# SL_LCD_SW_LED_2E.net
KiCad netlist of a schematic drawn in Altium Designer
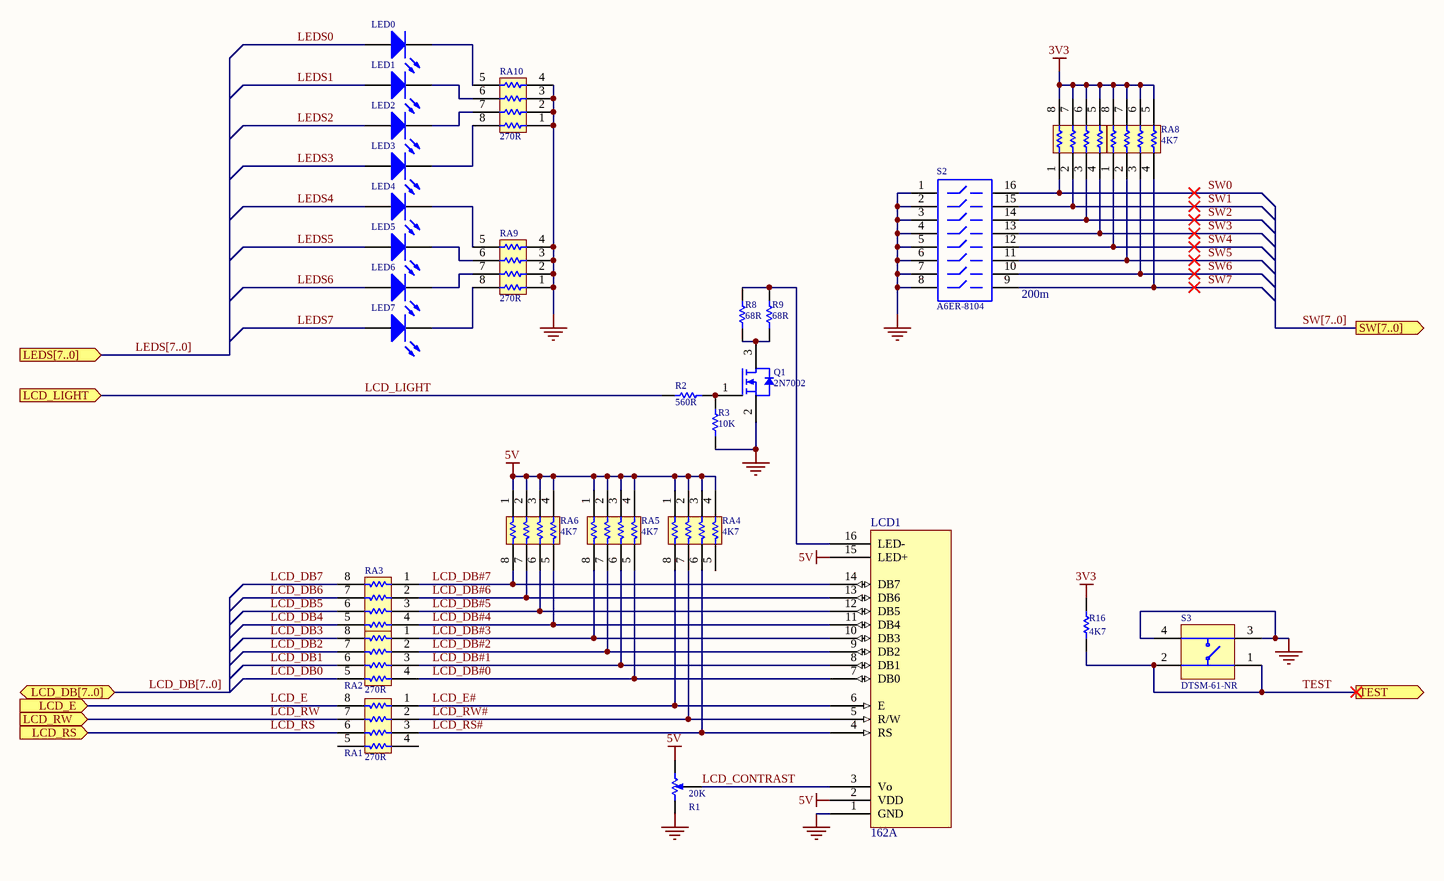
[diagram p0: SL_LCD_SW_LED_2E.SchDoc]

(export (version "E")
  (design (tool "Eeschema 10.0.6"))
  (components
    (comp (ref "LCD1")
      (value "162A")
      (footprint "Altium Nanoboard Project:162A")
      (description "16 char * 2 line LCD character display with b/light")
      (libsource (lib "Altium Nanoboard Project") (part "162A"))
    )
    (comp (ref "LED0")
      (value "HSMH-C170")
      (footprint "Altium Nanoboard Project:SMD _LED")
      (description "Typical RED GaAs SMD LED Agilent make")
      (libsource (lib "Altium Nanoboard Project") (part "HSMX-C670"))
    )
    (comp (ref "LED1")
      (value "HSMH-C170")
      (footprint "Altium Nanoboard Project:SMD _LED")
      (description "Typical RED GaAs SMD LED Agilent make")
      (libsource (lib "Altium Nanoboard Project") (part "HSMX-C670"))
    )
    (comp (ref "LED2")
      (value "HSMH-C170")
      (footprint "Altium Nanoboard Project:SMD _LED")
      (description "Typical RED GaAs SMD LED Agilent make")
      (libsource (lib "Altium Nanoboard Project") (part "HSMX-C670"))
    )
    (comp (ref "LED3")
      (value "HSMH-C170")
      (footprint "Altium Nanoboard Project:SMD _LED")
      (description "Typical RED GaAs SMD LED Agilent make")
      (libsource (lib "Altium Nanoboard Project") (part "HSMX-C670"))
    )
    (comp (ref "LED4")
      (value "HSMH-C170")
      (footprint "Altium Nanoboard Project:SMD _LED")
      (description "Typical RED GaAs SMD LED Agilent make")
      (libsource (lib "Altium Nanoboard Project") (part "HSMX-C670"))
    )
    (comp (ref "LED5")
      (value "HSMH-C170")
      (footprint "Altium Nanoboard Project:SMD _LED")
      (description "Typical RED GaAs SMD LED Agilent make")
      (libsource (lib "Altium Nanoboard Project") (part "HSMX-C670"))
    )
    (comp (ref "LED6")
      (value "HSMH-C170")
      (footprint "Altium Nanoboard Project:SMD _LED")
      (description "Typical RED GaAs SMD LED Agilent make")
      (libsource (lib "Altium Nanoboard Project") (part "HSMX-C670"))
    )
    (comp (ref "LED7")
      (value "HSMH-C170")
      (footprint "Altium Nanoboard Project:SMD _LED")
      (description "Typical RED GaAs SMD LED Agilent make")
      (libsource (lib "Altium Nanoboard Project") (part "HSMX-C670"))
    )
    (comp (ref "Q1")
      (value "2N7002")
      (footprint "Altium Nanoboard Project:SO-G3")
      (description "N Channel Mosfet")
      (libsource (lib "Altium Nanoboard Project") (part "2N7002"))
    )
    (comp (ref "R1")
      (value "20K")
      (footprint "POT4MM-2")
      (description "Square Trimming Potentiometer")
      (libsource (lib "Miscellaneous Devices") (part "RPot SM"))
    )
    (comp (ref "R2")
      (value "560R")
      (footprint "Altium Nanoboard Project:CC2012-0805")
      (description "Resistor")
      (libsource (lib "") (part "RES_1"))
    )
    (comp (ref "R3")
      (value "10K")
      (footprint "Altium Nanoboard Project:CC2012-0805")
      (description "Resistor")
      (libsource (lib "") (part "RES_1"))
    )
    (comp (ref "R8")
      (value "68R")
      (footprint "Altium Nanoboard Project:CC2012-0805")
      (description "Resistor")
      (libsource (lib "Altium Nanoboard Project") (part "RES"))
    )
    (comp (ref "R9")
      (value "68R")
      (footprint "Altium Nanoboard Project:CC2012-0805")
      (description "Resistor")
      (libsource (lib "Altium Nanoboard Project") (part "RES"))
    )
    (comp (ref "R16")
      (value "4K7")
      (footprint "Altium Nanoboard Project:CC2012-0805")
      (description "Resistor")
      (libsource (lib "") (part "RES_1"))
    )
    (comp (ref "RA1")
      (value "270R")
      (footprint "Altium Nanoboard Project:MNR34")
      (description "3216x4 Resistor Array")
      (libsource (lib "Altium Nanoboard Project") (part "MNR34"))
    )
    (comp (ref "RA2")
      (value "270R")
      (footprint "Altium Nanoboard Project:MNR34")
      (description "3216x4 Resistor Array")
      (libsource (lib "Altium Nanoboard Project") (part "MNR34"))
    )
    (comp (ref "RA3")
      (value "270R")
      (footprint "Altium Nanoboard Project:MNR34")
      (description "3216x4 Resistor Array")
      (libsource (lib "Altium Nanoboard Project") (part "MNR34"))
    )
    (comp (ref "RA4")
      (value "4K7")
      (footprint "MNR34T")
      (description "3216x4 Resistor Array")
      (libsource (lib "") (part "MNR34_2"))
    )
    (comp (ref "RA5")
      (value "4K7")
      (footprint "MNR34T")
      (description "3216x4 Resistor Array")
      (libsource (lib "") (part "MNR34_2"))
    )
    (comp (ref "RA6")
      (value "4K7")
      (footprint "MNR34T")
      (description "3216x4 Resistor Array")
      (libsource (lib "") (part "MNR34_2"))
    )
    (comp (ref "RA7")
      (value "4K7")
      (footprint "MNR34T")
      (description "3216x4 Resistor Array")
      (libsource (lib "") (part "MNR34_1"))
    )
    (comp (ref "RA8")
      (value "4K7")
      (footprint "MNR34T")
      (description "3216x4 Resistor Array")
      (libsource (lib "") (part "MNR34_1"))
    )
    (comp (ref "RA9")
      (value "270R")
      (footprint "MNR34T")
      (description "3216x4 Resistor Array")
      (libsource (lib "") (part "MNR34_3"))
    )
    (comp (ref "RA10")
      (value "270R")
      (footprint "MNR34T")
      (description "3216x4 Resistor Array")
      (libsource (lib "") (part "MNR34_3"))
    )
    (comp (ref "S2")
      (value "A6ER-8104")
      (footprint "Altium Nanoboard Project:DIP-16-KEY")
      (description "DIP Switch Side actuator long liver Piano Key")
      (fields (field (name "ALTIUM_VALUE") "200m"))
      (libsource (lib "Altium Nanoboard Project") (part "A6ER-8104"))
    )
    (comp (ref "S3")
      (value "DTSM-61-NR")
      (footprint "Altium Nanoboard Project:B3FS_SWITCH")
      (description "SPNA SMD Keyboard Switch")
      (libsource (lib "Altium Nanoboard Project") (part "B3FS"))
    )
  )
  (nets
    (net (code "1") (name "/LCD_CONTRAST") (class "Default")
      (node (ref "LCD1") (pin "3") (pinfunction "Vo_3") (pintype "tri_state"))
      (node (ref "R1") (pin "W") (pintype "passive"))
    )
    (net (code "2") (name "/LCD_DB#0") (class "Default")
      (node (ref "LCD1") (pin "7") (pinfunction "DB0_7") (pintype "bidirectional"))
      (node (ref "RA2") (pin "4") (pintype "passive"))
      (node (ref "RA5") (pin "5") (pintype "passive"))
    )
    (net (code "3") (name "/LCD_DB#1") (class "Default")
      (node (ref "LCD1") (pin "8") (pinfunction "DB1_8") (pintype "bidirectional"))
      (node (ref "RA2") (pin "3") (pintype "passive"))
      (node (ref "RA5") (pin "6") (pintype "passive"))
    )
    (net (code "4") (name "/LCD_DB#2") (class "Default")
      (node (ref "LCD1") (pin "9") (pinfunction "DB2_9") (pintype "bidirectional"))
      (node (ref "RA2") (pin "2") (pintype "passive"))
      (node (ref "RA5") (pin "7") (pintype "passive"))
    )
    (net (code "5") (name "/LCD_DB#3") (class "Default")
      (node (ref "LCD1") (pin "10") (pinfunction "DB3_10") (pintype "bidirectional"))
      (node (ref "RA2") (pin "1") (pintype "passive"))
      (node (ref "RA5") (pin "8") (pintype "passive"))
    )
    (net (code "6") (name "/LCD_DB#4") (class "Default")
      (node (ref "LCD1") (pin "11") (pinfunction "DB4_11") (pintype "bidirectional"))
      (node (ref "RA3") (pin "4") (pintype "passive"))
      (node (ref "RA6") (pin "5") (pintype "passive"))
    )
    (net (code "7") (name "/LCD_DB#5") (class "Default")
      (node (ref "LCD1") (pin "12") (pinfunction "DB5_12") (pintype "bidirectional"))
      (node (ref "RA3") (pin "3") (pintype "passive"))
      (node (ref "RA6") (pin "6") (pintype "passive"))
    )
    (net (code "8") (name "/LCD_DB#6") (class "Default")
      (node (ref "LCD1") (pin "13") (pinfunction "DB6_13") (pintype "bidirectional"))
      (node (ref "RA3") (pin "2") (pintype "passive"))
      (node (ref "RA6") (pin "7") (pintype "passive"))
    )
    (net (code "9") (name "/LCD_DB#7") (class "Default")
      (node (ref "LCD1") (pin "14") (pinfunction "DB7_14") (pintype "bidirectional"))
      (node (ref "RA3") (pin "1") (pintype "passive"))
      (node (ref "RA6") (pin "8") (pintype "passive"))
    )
    (net (code "10") (name "/LCD_DB0") (class "Default") (node (ref "RA2") (pin "5") (pintype "passive")))
    (net (code "11") (name "/LCD_DB1") (class "Default") (node (ref "RA2") (pin "6") (pintype "passive")))
    (net (code "12") (name "/LCD_DB2") (class "Default") (node (ref "RA2") (pin "7") (pintype "passive")))
    (net (code "13") (name "/LCD_DB3") (class "Default") (node (ref "RA2") (pin "8") (pintype "passive")))
    (net (code "14") (name "/LCD_DB4") (class "Default") (node (ref "RA3") (pin "5") (pintype "passive")))
    (net (code "15") (name "/LCD_DB5") (class "Default") (node (ref "RA3") (pin "6") (pintype "passive")))
    (net (code "16") (name "/LCD_DB6") (class "Default") (node (ref "RA3") (pin "7") (pintype "passive")))
    (net (code "17") (name "/LCD_DB7") (class "Default") (node (ref "RA3") (pin "8") (pintype "passive")))
    (net (code "19") (name "/LCD_E") (class "Default") (node (ref "RA1") (pin "8") (pintype "passive")))
    (net (code "20") (name "/LCD_E#") (class "Default")
      (node (ref "LCD1") (pin "6") (pinfunction "E_6") (pintype "input"))
      (node (ref "RA1") (pin "1") (pintype "passive"))
      (node (ref "RA4") (pin "8") (pintype "passive"))
    )
    (net (code "21") (name "/LCD_LIGHT") (class "Default")
      (node (ref "R2") (pin "1") (pinfunction "1_1") (pintype "passive"))
    )
    (net (code "22") (name "/LCD_RS") (class "Default") (node (ref "RA1") (pin "6") (pintype "passive")))
    (net (code "23") (name "/LCD_RS#") (class "Default")
      (node (ref "LCD1") (pin "4") (pinfunction "RS_4") (pintype "input"))
      (node (ref "RA1") (pin "3") (pintype "passive"))
      (node (ref "RA4") (pin "6") (pintype "passive"))
    )
    (net (code "24") (name "/LCD_RW") (class "Default") (node (ref "RA1") (pin "7") (pintype "passive")))
    (net (code "25") (name "/LCD_RW#") (class "Default")
      (node (ref "LCD1") (pin "5") (pinfunction "R/W_5") (pintype "input"))
      (node (ref "RA1") (pin "2") (pintype "passive"))
      (node (ref "RA4") (pin "7") (pintype "passive"))
    )
    (net (code "26") (name "/LEDS0") (class "Default")
      (node (ref "LED0") (pin "1") (pinfunction "A_1") (pintype "passive"))
    )
    (net (code "27") (name "/LEDS1") (class "Default")
      (node (ref "LED1") (pin "1") (pinfunction "A_1") (pintype "passive"))
    )
    (net (code "28") (name "/LEDS2") (class "Default")
      (node (ref "LED2") (pin "1") (pinfunction "A_1") (pintype "passive"))
    )
    (net (code "29") (name "/LEDS3") (class "Default")
      (node (ref "LED3") (pin "1") (pinfunction "A_1") (pintype "passive"))
    )
    (net (code "30") (name "/LEDS4") (class "Default")
      (node (ref "LED4") (pin "1") (pinfunction "A_1") (pintype "passive"))
    )
    (net (code "31") (name "/LEDS5") (class "Default")
      (node (ref "LED5") (pin "1") (pinfunction "A_1") (pintype "passive"))
    )
    (net (code "32") (name "/LEDS6") (class "Default")
      (node (ref "LED6") (pin "1") (pinfunction "A_1") (pintype "passive"))
    )
    (net (code "33") (name "/LEDS7") (class "Default")
      (node (ref "LED7") (pin "1") (pinfunction "A_1") (pintype "passive"))
    )
    (net (code "35") (name "/SW0") (class "Default")
      (node (ref "RA7") (pin "1") (pintype "passive"))
      (node (ref "S2") (pin "16") (pinfunction "16_16") (pintype "passive"))
    )
    (net (code "36") (name "/SW1") (class "Default")
      (node (ref "RA7") (pin "2") (pintype "passive"))
      (node (ref "S2") (pin "15") (pinfunction "15_15") (pintype "passive"))
    )
    (net (code "37") (name "/SW2") (class "Default")
      (node (ref "RA7") (pin "3") (pintype "passive"))
      (node (ref "S2") (pin "14") (pinfunction "14_14") (pintype "passive"))
    )
    (net (code "38") (name "/SW3") (class "Default")
      (node (ref "RA7") (pin "4") (pintype "passive"))
      (node (ref "S2") (pin "13") (pinfunction "13_13") (pintype "passive"))
    )
    (net (code "39") (name "/SW4") (class "Default")
      (node (ref "RA8") (pin "1") (pintype "passive"))
      (node (ref "S2") (pin "12") (pinfunction "12_12") (pintype "passive"))
    )
    (net (code "40") (name "/SW5") (class "Default")
      (node (ref "RA8") (pin "2") (pintype "passive"))
      (node (ref "S2") (pin "11") (pinfunction "11_11") (pintype "passive"))
    )
    (net (code "41") (name "/SW6") (class "Default")
      (node (ref "RA8") (pin "3") (pintype "passive"))
      (node (ref "S2") (pin "10") (pinfunction "10_10") (pintype "passive"))
    )
    (net (code "42") (name "/SW7") (class "Default")
      (node (ref "RA8") (pin "4") (pintype "passive"))
      (node (ref "S2") (pin "9") (pinfunction "9_9") (pintype "passive"))
    )
    (net (code "44") (name "/TEST") (class "Default")
      (node (ref "R16") (pin "2") (pinfunction "2_2") (pintype "passive"))
      (node (ref "S3") (pin "1") (pinfunction "1_1") (pintype "passive"))
      (node (ref "S3") (pin "2") (pinfunction "2_2") (pintype "passive"))
    )
    (net (code "45") (name "3V3") (class "Default")
      (node (ref "R16") (pin "1") (pinfunction "1_1") (pintype "passive"))
      (node (ref "RA7") (pin "5") (pintype "passive"))
      (node (ref "RA7") (pin "6") (pintype "passive"))
      (node (ref "RA7") (pin "7") (pintype "passive"))
      (node (ref "RA7") (pin "8") (pintype "passive"))
      (node (ref "RA8") (pin "5") (pintype "passive"))
      (node (ref "RA8") (pin "6") (pintype "passive"))
      (node (ref "RA8") (pin "7") (pintype "passive"))
      (node (ref "RA8") (pin "8") (pintype "passive"))
    )
    (net (code "46") (name "5V") (class "Default")
      (node (ref "LCD1") (pin "15") (pinfunction "LED+_15") (pintype "power_in"))
      (node (ref "LCD1") (pin "2") (pinfunction "VDD_2") (pintype "power_in"))
      (node (ref "R1") (pin "CW") (pinfunction "+_CW") (pintype "passive"))
      (node (ref "RA4") (pin "1") (pintype "passive"))
      (node (ref "RA4") (pin "2") (pintype "passive"))
      (node (ref "RA4") (pin "3") (pintype "passive"))
      (node (ref "RA4") (pin "4") (pintype "passive"))
      (node (ref "RA5") (pin "1") (pintype "passive"))
      (node (ref "RA5") (pin "2") (pintype "passive"))
      (node (ref "RA5") (pin "3") (pintype "passive"))
      (node (ref "RA5") (pin "4") (pintype "passive"))
      (node (ref "RA6") (pin "1") (pintype "passive"))
      (node (ref "RA6") (pin "2") (pintype "passive"))
      (node (ref "RA6") (pin "3") (pintype "passive"))
      (node (ref "RA6") (pin "4") (pintype "passive"))
    )
    (net (code "47") (name "GND") (class "Default")
      (node (ref "LCD1") (pin "1") (pinfunction "GND_1") (pintype "power_in"))
      (node (ref "Q1") (pin "2") (pintype "passive"))
      (node (ref "R1") (pin "CCW") (pinfunction "-_CCW") (pintype "passive"))
      (node (ref "R3") (pin "1") (pinfunction "1_1") (pintype "passive"))
      (node (ref "RA10") (pin "1") (pintype "passive"))
      (node (ref "RA10") (pin "2") (pintype "passive"))
      (node (ref "RA10") (pin "3") (pintype "passive"))
      (node (ref "RA10") (pin "4") (pintype "passive"))
      (node (ref "RA9") (pin "1") (pintype "passive"))
      (node (ref "RA9") (pin "2") (pintype "passive"))
      (node (ref "RA9") (pin "3") (pintype "passive"))
      (node (ref "RA9") (pin "4") (pintype "passive"))
      (node (ref "S2") (pin "1") (pinfunction "1_1") (pintype "passive"))
      (node (ref "S2") (pin "2") (pinfunction "2_2") (pintype "passive"))
      (node (ref "S2") (pin "3") (pinfunction "3_3") (pintype "passive"))
      (node (ref "S2") (pin "4") (pinfunction "4_4") (pintype "passive"))
      (node (ref "S2") (pin "5") (pinfunction "5_5") (pintype "passive"))
      (node (ref "S2") (pin "6") (pinfunction "6_6") (pintype "passive"))
      (node (ref "S2") (pin "7") (pinfunction "7_7") (pintype "passive"))
      (node (ref "S2") (pin "8") (pinfunction "8_8") (pintype "passive"))
      (node (ref "S3") (pin "3") (pinfunction "3_3") (pintype "passive"))
      (node (ref "S3") (pin "4") (pinfunction "4_4") (pintype "passive"))
    )
    (net (code "48") (name "Net-(LCD1-LED-)") (class "Default")
      (node (ref "LCD1") (pin "16") (pinfunction "LED-_16") (pintype "power_in"))
      (node (ref "R8") (pin "1") (pinfunction "1_1") (pintype "passive"))
      (node (ref "R9") (pin "1") (pinfunction "1_1") (pintype "passive"))
    )
    (net (code "49") (name "Net-(LED0-K)") (class "Default")
      (node (ref "LED0") (pin "2") (pinfunction "K_2") (pintype "passive"))
      (node (ref "RA10") (pin "5") (pintype "passive"))
    )
    (net (code "50") (name "Net-(LED1-K)") (class "Default")
      (node (ref "LED1") (pin "2") (pinfunction "K_2") (pintype "passive"))
      (node (ref "RA10") (pin "6") (pintype "passive"))
    )
    (net (code "51") (name "Net-(LED2-K)") (class "Default")
      (node (ref "LED2") (pin "2") (pinfunction "K_2") (pintype "passive"))
      (node (ref "RA10") (pin "7") (pintype "passive"))
    )
    (net (code "52") (name "Net-(LED3-K)") (class "Default")
      (node (ref "LED3") (pin "2") (pinfunction "K_2") (pintype "passive"))
      (node (ref "RA10") (pin "8") (pintype "passive"))
    )
    (net (code "53") (name "Net-(LED4-K)") (class "Default")
      (node (ref "LED4") (pin "2") (pinfunction "K_2") (pintype "passive"))
      (node (ref "RA9") (pin "5") (pintype "passive"))
    )
    (net (code "54") (name "Net-(LED5-K)") (class "Default")
      (node (ref "LED5") (pin "2") (pinfunction "K_2") (pintype "passive"))
      (node (ref "RA9") (pin "6") (pintype "passive"))
    )
    (net (code "55") (name "Net-(LED6-K)") (class "Default")
      (node (ref "LED6") (pin "2") (pinfunction "K_2") (pintype "passive"))
      (node (ref "RA9") (pin "7") (pintype "passive"))
    )
    (net (code "56") (name "Net-(LED7-K)") (class "Default")
      (node (ref "LED7") (pin "2") (pinfunction "K_2") (pintype "passive"))
      (node (ref "RA9") (pin "8") (pintype "passive"))
    )
    (net (code "57") (name "Net-(Q1-Pad1)") (class "Default")
      (node (ref "Q1") (pin "1") (pintype "passive"))
      (node (ref "R2") (pin "2") (pinfunction "2_2") (pintype "passive"))
      (node (ref "R3") (pin "2") (pinfunction "2_2") (pintype "passive"))
    )
    (net (code "58") (name "Net-(Q1-Pad3)") (class "Default")
      (node (ref "Q1") (pin "3") (pintype "passive"))
      (node (ref "R8") (pin "2") (pinfunction "2_2") (pintype "passive"))
      (node (ref "R9") (pin "2") (pinfunction "2_2") (pintype "passive"))
    )
    (net (code "59") (name "unconnected-(RA1-Pad4)") (class "Default")
      (node (ref "RA1") (pin "4") (pintype "passive"))
    )
    (net (code "60") (name "unconnected-(RA1-Pad5)") (class "Default")
      (node (ref "RA1") (pin "5") (pintype "passive"))
    )
    (net (code "61") (name "unconnected-(RA4-Pad5)") (class "Default")
      (node (ref "RA4") (pin "5") (pintype "passive"))
    )
  )
)
